# Flex-LED.net
KiCad netlist of a schematic drawn in Altium Designer
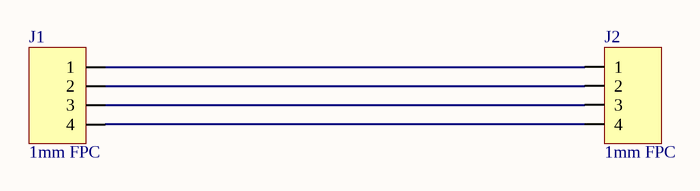
[diagram p0: Flex-LED.SchDoc]

(export (version "E")
  (design (tool "Eeschema 10.0.6"))
  (components
    (comp (ref "J1")
      (value "1mm FPC")
      (footprint "FPC-1mm-4P")
      (description "1mm Pitch 4P FPC")
      (libsource (lib "LED-Driver-Library") (part "FPC-1mm-4P"))
    )
    (comp (ref "J2")
      (value "1mm FPC")
      (footprint "FPC-1mm-4P")
      (description "1mm Pitch 4P FPC")
      (libsource (lib "") (part "FPC-1mm-4P_1"))
    )
  )
  (nets
    (net (code "1") (name "Net-(J1-Pad1)") (class "Default")
      (node (ref "J1") (pin "1") (pinfunction "1_1") (pintype "passive"))
      (node (ref "J2") (pin "1") (pinfunction "1_1") (pintype "passive"))
    )
    (net (code "2") (name "Net-(J1-Pad2)") (class "Default")
      (node (ref "J1") (pin "2") (pinfunction "2_2") (pintype "passive"))
      (node (ref "J2") (pin "2") (pinfunction "2_2") (pintype "passive"))
    )
    (net (code "3") (name "Net-(J1-Pad3)") (class "Default")
      (node (ref "J1") (pin "3") (pinfunction "3_3") (pintype "passive"))
      (node (ref "J2") (pin "3") (pinfunction "3_3") (pintype "passive"))
    )
    (net (code "4") (name "Net-(J1-Pad4)") (class "Default")
      (node (ref "J1") (pin "4") (pinfunction "4_4") (pintype "passive"))
      (node (ref "J2") (pin "4") (pinfunction "4_4") (pintype "passive"))
    )
  )
)
